# IR.net
KiCad netlist of a schematic drawn in EAGLE
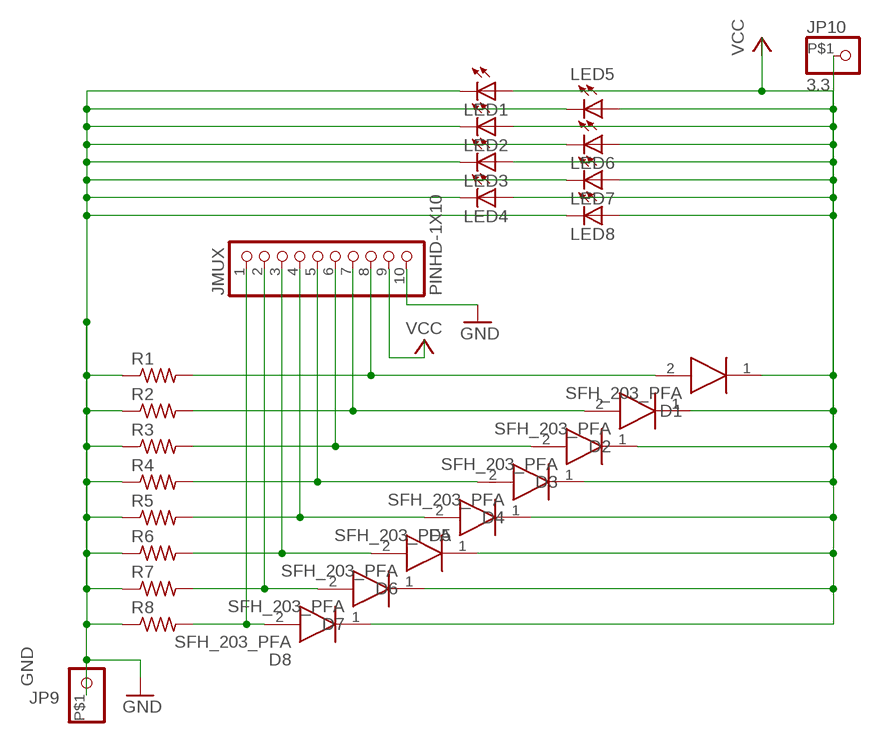
[diagram p0: schematic, sheet 1]

(export (version "E")
  (design (tool "Eeschema 10.0.6"))
  (components
    (comp (ref "D1")
      (value "SFH_203_PFA")
      (footprint "eagle-import:SFH213_1")
      (fields
        (field (name "MANUFACTURER_PART_NUMBER") "SFH 203 PFA")
        (field (name "MOUSER_PART_NUMBER") "720-SFH203PFA")
        (field (name "RS_PART_NUMBER") "6548665")
      )
      (libsource (lib "eagle-import") (part "SFH_203_PFA"))
    )
    (comp (ref "D2")
      (value "SFH_203_PFA")
      (footprint "eagle-import:SFH213_1")
      (fields
        (field (name "MANUFACTURER_PART_NUMBER") "SFH 203 PFA")
        (field (name "MOUSER_PART_NUMBER") "720-SFH203PFA")
        (field (name "RS_PART_NUMBER") "6548665")
      )
      (libsource (lib "eagle-import") (part "SFH_203_PFA"))
    )
    (comp (ref "D3")
      (value "SFH_203_PFA")
      (footprint "eagle-import:SFH213_1")
      (fields
        (field (name "MANUFACTURER_PART_NUMBER") "SFH 203 PFA")
        (field (name "MOUSER_PART_NUMBER") "720-SFH203PFA")
        (field (name "RS_PART_NUMBER") "6548665")
      )
      (libsource (lib "eagle-import") (part "SFH_203_PFA"))
    )
    (comp (ref "D4")
      (value "SFH_203_PFA")
      (footprint "eagle-import:SFH213_1")
      (fields
        (field (name "MANUFACTURER_PART_NUMBER") "SFH 203 PFA")
        (field (name "MOUSER_PART_NUMBER") "720-SFH203PFA")
        (field (name "RS_PART_NUMBER") "6548665")
      )
      (libsource (lib "eagle-import") (part "SFH_203_PFA"))
    )
    (comp (ref "D5")
      (value "SFH_203_PFA")
      (footprint "eagle-import:SFH213_1")
      (fields
        (field (name "MANUFACTURER_PART_NUMBER") "SFH 203 PFA")
        (field (name "MOUSER_PART_NUMBER") "720-SFH203PFA")
        (field (name "RS_PART_NUMBER") "6548665")
      )
      (libsource (lib "eagle-import") (part "SFH_203_PFA"))
    )
    (comp (ref "D6")
      (value "SFH_203_PFA")
      (footprint "eagle-import:SFH213_1")
      (fields
        (field (name "MANUFACTURER_PART_NUMBER") "SFH 203 PFA")
        (field (name "MOUSER_PART_NUMBER") "720-SFH203PFA")
        (field (name "RS_PART_NUMBER") "6548665")
      )
      (libsource (lib "eagle-import") (part "SFH_203_PFA"))
    )
    (comp (ref "D7")
      (value "SFH_203_PFA")
      (footprint "eagle-import:SFH213_1")
      (fields
        (field (name "MANUFACTURER_PART_NUMBER") "SFH 203 PFA")
        (field (name "MOUSER_PART_NUMBER") "720-SFH203PFA")
        (field (name "RS_PART_NUMBER") "6548665")
      )
      (libsource (lib "eagle-import") (part "SFH_203_PFA"))
    )
    (comp (ref "D8")
      (value "SFH_203_PFA")
      (footprint "eagle-import:SFH213_1")
      (fields
        (field (name "MANUFACTURER_PART_NUMBER") "SFH 203 PFA")
        (field (name "MOUSER_PART_NUMBER") "720-SFH203PFA")
        (field (name "RS_PART_NUMBER") "6548665")
      )
      (libsource (lib "eagle-import") (part "SFH_203_PFA"))
    )
    (comp (ref "JMUX")
      (value "PINHD-1X10")
      (footprint "eagle-import:1X10-BIG")
      (libsource (lib "eagle-import") (part "PINHD-1X10"))
    )
    (comp (ref "JP9")
      (value "GND")
      (footprint "eagle-import:1X1-BIGPOGO")
      (libsource (lib "eagle-import") (part "PINHD-1X1-BIGPOGO"))
    )
    (comp (ref "JP10")
      (value "3.3")
      (footprint "eagle-import:1X1-BIGPOGO")
      (libsource (lib "eagle-import") (part "PINHD-1X1-BIGPOGO"))
    )
    (comp (ref "LED1")
      (value "LED5MM")
      (footprint "eagle-import:LED5MM")
      (libsource (lib "eagle-import") (part "LED5MM"))
    )
    (comp (ref "LED2")
      (value "LED5MM")
      (footprint "eagle-import:LED5MM")
      (libsource (lib "eagle-import") (part "LED5MM"))
    )
    (comp (ref "LED3")
      (value "LED5MM")
      (footprint "eagle-import:LED5MM")
      (libsource (lib "eagle-import") (part "LED5MM"))
    )
    (comp (ref "LED4")
      (value "LED5MM")
      (footprint "eagle-import:LED5MM")
      (libsource (lib "eagle-import") (part "LED5MM"))
    )
    (comp (ref "LED5")
      (value "LED5MM")
      (footprint "eagle-import:LED5MM")
      (libsource (lib "eagle-import") (part "LED5MM"))
    )
    (comp (ref "LED6")
      (value "LED5MM")
      (footprint "eagle-import:LED5MM")
      (libsource (lib "eagle-import") (part "LED5MM"))
    )
    (comp (ref "LED7")
      (value "LED5MM")
      (footprint "eagle-import:LED5MM")
      (libsource (lib "eagle-import") (part "LED5MM"))
    )
    (comp (ref "LED8")
      (value "LED5MM")
      (footprint "eagle-import:LED5MM")
      (libsource (lib "eagle-import") (part "LED5MM"))
    )
    (comp (ref "R1")
      (value "R-US_0207/10")
      (footprint "eagle-import:0207_10")
      (libsource (lib "eagle-import") (part "R-US_0207/10"))
    )
    (comp (ref "R2")
      (value "R-US_0207/10")
      (footprint "eagle-import:0207_10")
      (libsource (lib "eagle-import") (part "R-US_0207/10"))
    )
    (comp (ref "R3")
      (value "R-US_0207/10")
      (footprint "eagle-import:0207_10")
      (libsource (lib "eagle-import") (part "R-US_0207/10"))
    )
    (comp (ref "R4")
      (value "R-US_0207/10")
      (footprint "eagle-import:0207_10")
      (libsource (lib "eagle-import") (part "R-US_0207/10"))
    )
    (comp (ref "R5")
      (value "R-US_0207/10")
      (footprint "eagle-import:0207_10")
      (libsource (lib "eagle-import") (part "R-US_0207/10"))
    )
    (comp (ref "R6")
      (value "R-US_0207/10")
      (footprint "eagle-import:0207_10")
      (libsource (lib "eagle-import") (part "R-US_0207/10"))
    )
    (comp (ref "R7")
      (value "R-US_0207/10")
      (footprint "eagle-import:0207_10")
      (libsource (lib "eagle-import") (part "R-US_0207/10"))
    )
    (comp (ref "R8")
      (value "R-US_0207/10")
      (footprint "eagle-import:0207_10")
      (libsource (lib "eagle-import") (part "R-US_0207/10"))
    )
  )
  (nets
    (net (code "1") (name "GND") (class "Default")
      (node (ref "JMUX") (pin "10") (pinfunction "10_10") (pintype "passive"))
      (node (ref "JP9") (pin "P$1") (pinfunction "1_P$1") (pintype "passive"))
      (node (ref "LED1") (pin "K") (pinfunction "C_K") (pintype "passive"))
      (node (ref "LED2") (pin "K") (pinfunction "C_K") (pintype "passive"))
      (node (ref "LED3") (pin "K") (pinfunction "C_K") (pintype "passive"))
      (node (ref "LED4") (pin "K") (pinfunction "C_K") (pintype "passive"))
      (node (ref "LED5") (pin "K") (pinfunction "C_K") (pintype "passive"))
      (node (ref "LED6") (pin "K") (pinfunction "C_K") (pintype "passive"))
      (node (ref "LED7") (pin "K") (pinfunction "C_K") (pintype "passive"))
      (node (ref "LED8") (pin "K") (pinfunction "C_K") (pintype "passive"))
      (node (ref "R1") (pin "1") (pinfunction "1_1") (pintype "passive"))
      (node (ref "R2") (pin "1") (pinfunction "1_1") (pintype "passive"))
      (node (ref "R3") (pin "1") (pinfunction "1_1") (pintype "passive"))
      (node (ref "R4") (pin "1") (pinfunction "1_1") (pintype "passive"))
      (node (ref "R5") (pin "1") (pinfunction "1_1") (pintype "passive"))
      (node (ref "R6") (pin "1") (pinfunction "1_1") (pintype "passive"))
      (node (ref "R7") (pin "1") (pinfunction "1_1") (pintype "passive"))
      (node (ref "R8") (pin "1") (pinfunction "1_1") (pintype "passive"))
    )
    (net (code "2") (name "Net-(D1-A)") (class "Default")
      (node (ref "D1") (pin "2") (pinfunction "A_2") (pintype "bidirectional"))
      (node (ref "JMUX") (pin "8") (pinfunction "8_8") (pintype "passive"))
      (node (ref "R1") (pin "2") (pinfunction "2_2") (pintype "passive"))
    )
    (net (code "3") (name "Net-(D2-A)") (class "Default")
      (node (ref "D2") (pin "2") (pinfunction "A_2") (pintype "bidirectional"))
      (node (ref "JMUX") (pin "7") (pinfunction "7_7") (pintype "passive"))
      (node (ref "R2") (pin "2") (pinfunction "2_2") (pintype "passive"))
    )
    (net (code "4") (name "Net-(D3-A)") (class "Default")
      (node (ref "D3") (pin "2") (pinfunction "A_2") (pintype "bidirectional"))
      (node (ref "JMUX") (pin "6") (pinfunction "6_6") (pintype "passive"))
      (node (ref "R3") (pin "2") (pinfunction "2_2") (pintype "passive"))
    )
    (net (code "5") (name "Net-(D4-A)") (class "Default")
      (node (ref "D4") (pin "2") (pinfunction "A_2") (pintype "bidirectional"))
      (node (ref "JMUX") (pin "5") (pinfunction "5_5") (pintype "passive"))
      (node (ref "R4") (pin "2") (pinfunction "2_2") (pintype "passive"))
    )
    (net (code "6") (name "Net-(D5-A)") (class "Default")
      (node (ref "D5") (pin "2") (pinfunction "A_2") (pintype "bidirectional"))
      (node (ref "JMUX") (pin "4") (pinfunction "4_4") (pintype "passive"))
      (node (ref "R5") (pin "2") (pinfunction "2_2") (pintype "passive"))
    )
    (net (code "7") (name "Net-(D6-A)") (class "Default")
      (node (ref "D6") (pin "2") (pinfunction "A_2") (pintype "bidirectional"))
      (node (ref "JMUX") (pin "3") (pinfunction "3_3") (pintype "passive"))
      (node (ref "R6") (pin "2") (pinfunction "2_2") (pintype "passive"))
    )
    (net (code "8") (name "Net-(D7-A)") (class "Default")
      (node (ref "D7") (pin "2") (pinfunction "A_2") (pintype "bidirectional"))
      (node (ref "JMUX") (pin "2") (pinfunction "2_2") (pintype "passive"))
      (node (ref "R7") (pin "2") (pinfunction "2_2") (pintype "passive"))
    )
    (net (code "9") (name "Net-(D8-A)") (class "Default")
      (node (ref "D8") (pin "2") (pinfunction "A_2") (pintype "bidirectional"))
      (node (ref "JMUX") (pin "1") (pinfunction "1_1") (pintype "passive"))
      (node (ref "R8") (pin "2") (pinfunction "2_2") (pintype "passive"))
    )
    (net (code "10") (name "VCC") (class "Default")
      (node (ref "D1") (pin "1") (pinfunction "K_1") (pintype "bidirectional"))
      (node (ref "D2") (pin "1") (pinfunction "K_1") (pintype "bidirectional"))
      (node (ref "D3") (pin "1") (pinfunction "K_1") (pintype "bidirectional"))
      (node (ref "D4") (pin "1") (pinfunction "K_1") (pintype "bidirectional"))
      (node (ref "D5") (pin "1") (pinfunction "K_1") (pintype "bidirectional"))
      (node (ref "D6") (pin "1") (pinfunction "K_1") (pintype "bidirectional"))
      (node (ref "D7") (pin "1") (pinfunction "K_1") (pintype "bidirectional"))
      (node (ref "D8") (pin "1") (pinfunction "K_1") (pintype "bidirectional"))
      (node (ref "JMUX") (pin "9") (pinfunction "9_9") (pintype "passive"))
      (node (ref "JP10") (pin "P$1") (pinfunction "1_P$1") (pintype "passive"))
      (node (ref "LED1") (pin "A") (pinfunction "A_A") (pintype "passive"))
      (node (ref "LED2") (pin "A") (pinfunction "A_A") (pintype "passive"))
      (node (ref "LED3") (pin "A") (pinfunction "A_A") (pintype "passive"))
      (node (ref "LED4") (pin "A") (pinfunction "A_A") (pintype "passive"))
      (node (ref "LED5") (pin "A") (pinfunction "A_A") (pintype "passive"))
      (node (ref "LED6") (pin "A") (pinfunction "A_A") (pintype "passive"))
      (node (ref "LED7") (pin "A") (pinfunction "A_A") (pintype "passive"))
      (node (ref "LED8") (pin "A") (pinfunction "A_A") (pintype "passive"))
    )
  )
)
